# dual-mux.net
KiCad netlist of a schematic drawn in EAGLE
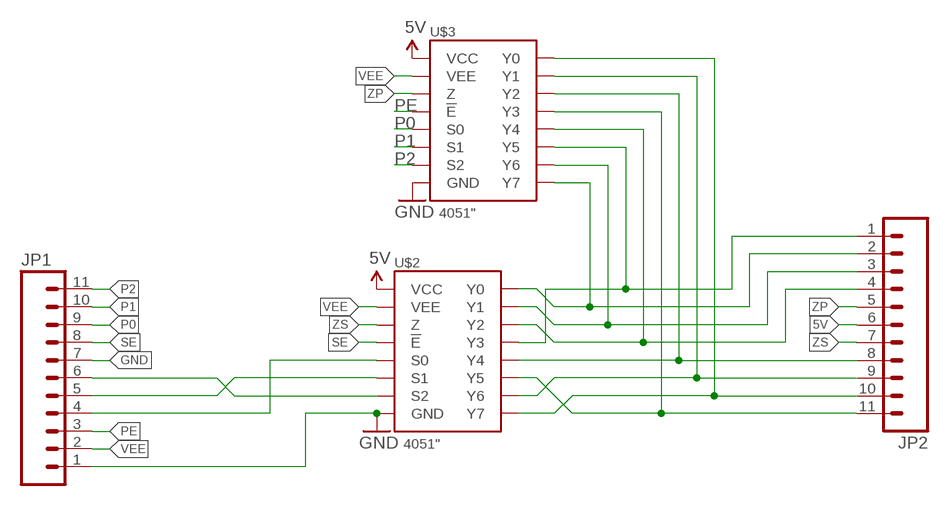
[diagram p0: schematic, sheet 1]

(export (version "E")
  (design (tool "Eeschema 10.0.6"))
  (components
    (comp (ref "JP1")
      (value "M11LONGPADS")
      (footprint "eagle-import:1X11_LONGPADS")
      (libsource (lib "eagle-import") (part "M11LONGPADS"))
    )
    (comp (ref "JP2")
      (value "M11LONGPADS")
      (footprint "eagle-import:1X11_LONGPADS")
      (libsource (lib "eagle-import") (part "M11LONGPADS"))
    )
    (comp (ref "U$2")
      (value "4051\"")
      (footprint "eagle-import:TSSOP-16")
      (libsource (lib "eagle-import") (part "4051{dblquote}"))
    )
    (comp (ref "U$3")
      (value "4051\"")
      (footprint "eagle-import:TSSOP-16")
      (libsource (lib "eagle-import") (part "4051{dblquote}"))
    )
  )
  (nets
    (net (code "1") (name "5V") (class "Default")
      (node (ref "JP2") (pin "6") (pinfunction "6_6") (pintype "passive"))
      (node (ref "U$2") (pin "P$16") (pinfunction "VCC_P$16") (pintype "bidirectional"))
      (node (ref "U$3") (pin "P$16") (pinfunction "VCC_P$16") (pintype "bidirectional"))
    )
    (net (code "2") (name "GND") (class "Default")
      (node (ref "JP1") (pin "1") (pinfunction "1_1") (pintype "passive"))
      (node (ref "JP1") (pin "7") (pinfunction "7_7") (pintype "passive"))
      (node (ref "U$2") (pin "P$8") (pinfunction "GND_P$8") (pintype "bidirectional"))
      (node (ref "U$3") (pin "P$8") (pinfunction "GND_P$8") (pintype "bidirectional"))
    )
    (net (code "3") (name "Net-(U$2-S0)") (class "Default")
      (node (ref "JP1") (pin "4") (pinfunction "4_4") (pintype "passive"))
      (node (ref "U$2") (pin "P$11") (pinfunction "S0_P$11") (pintype "bidirectional"))
    )
    (net (code "4") (name "Net-(U$2-S1)") (class "Default")
      (node (ref "JP1") (pin "5") (pinfunction "5_5") (pintype "passive"))
      (node (ref "U$2") (pin "P$10") (pinfunction "S1_P$10") (pintype "bidirectional"))
    )
    (net (code "5") (name "Net-(U$2-S2)") (class "Default")
      (node (ref "JP1") (pin "6") (pinfunction "6_6") (pintype "passive"))
      (node (ref "U$2") (pin "P$9") (pinfunction "S2_P$9") (pintype "bidirectional"))
    )
    (net (code "6") (name "Net-(U$2-Y0)") (class "Default")
      (node (ref "JP2") (pin "2") (pinfunction "2_2") (pintype "passive"))
      (node (ref "U$2") (pin "P$13") (pinfunction "Y0_P$13") (pintype "bidirectional"))
      (node (ref "U$3") (pin "P$4") (pinfunction "Y7_P$4") (pintype "bidirectional"))
    )
    (net (code "7") (name "Net-(U$2-Y1)") (class "Default")
      (node (ref "JP2") (pin "3") (pinfunction "3_3") (pintype "passive"))
      (node (ref "U$2") (pin "P$14") (pinfunction "Y1_P$14") (pintype "bidirectional"))
      (node (ref "U$3") (pin "P$2") (pinfunction "Y6_P$2") (pintype "bidirectional"))
    )
    (net (code "8") (name "Net-(U$2-Y2)") (class "Default")
      (node (ref "JP2") (pin "4") (pinfunction "4_4") (pintype "passive"))
      (node (ref "U$2") (pin "P$15") (pinfunction "Y2_P$15") (pintype "bidirectional"))
      (node (ref "U$3") (pin "P$1") (pinfunction "Y4_P$1") (pintype "bidirectional"))
    )
    (net (code "9") (name "Net-(U$2-Y3)") (class "Default")
      (node (ref "JP2") (pin "1") (pinfunction "1_1") (pintype "passive"))
      (node (ref "U$2") (pin "P$12") (pinfunction "Y3_P$12") (pintype "bidirectional"))
      (node (ref "U$3") (pin "P$5") (pinfunction "Y5_P$5") (pintype "bidirectional"))
    )
    (net (code "10") (name "Net-(U$2-Y4)") (class "Default")
      (node (ref "JP2") (pin "8") (pinfunction "8_8") (pintype "passive"))
      (node (ref "U$2") (pin "P$1") (pinfunction "Y4_P$1") (pintype "bidirectional"))
      (node (ref "U$3") (pin "P$15") (pinfunction "Y2_P$15") (pintype "bidirectional"))
    )
    (net (code "11") (name "Net-(U$2-Y5)") (class "Default")
      (node (ref "JP2") (pin "11") (pinfunction "11_11") (pintype "passive"))
      (node (ref "U$2") (pin "P$5") (pinfunction "Y5_P$5") (pintype "bidirectional"))
      (node (ref "U$3") (pin "P$12") (pinfunction "Y3_P$12") (pintype "bidirectional"))
    )
    (net (code "12") (name "Net-(U$2-Y6)") (class "Default")
      (node (ref "JP2") (pin "9") (pinfunction "9_9") (pintype "passive"))
      (node (ref "U$2") (pin "P$2") (pinfunction "Y6_P$2") (pintype "bidirectional"))
      (node (ref "U$3") (pin "P$14") (pinfunction "Y1_P$14") (pintype "bidirectional"))
    )
    (net (code "13") (name "Net-(U$2-Y7)") (class "Default")
      (node (ref "JP2") (pin "10") (pinfunction "10_10") (pintype "passive"))
      (node (ref "U$2") (pin "P$4") (pinfunction "Y7_P$4") (pintype "bidirectional"))
      (node (ref "U$3") (pin "P$13") (pinfunction "Y0_P$13") (pintype "bidirectional"))
    )
    (net (code "14") (name "P0") (class "Default")
      (node (ref "JP1") (pin "9") (pinfunction "9_9") (pintype "passive"))
      (node (ref "U$3") (pin "P$11") (pinfunction "S0_P$11") (pintype "bidirectional"))
    )
    (net (code "15") (name "P1") (class "Default")
      (node (ref "JP1") (pin "10") (pinfunction "10_10") (pintype "passive"))
      (node (ref "U$3") (pin "P$10") (pinfunction "S1_P$10") (pintype "bidirectional"))
    )
    (net (code "16") (name "P2") (class "Default")
      (node (ref "JP1") (pin "11") (pinfunction "11_11") (pintype "passive"))
      (node (ref "U$3") (pin "P$9") (pinfunction "S2_P$9") (pintype "bidirectional"))
    )
    (net (code "17") (name "PE") (class "Default")
      (node (ref "JP1") (pin "3") (pinfunction "3_3") (pintype "passive"))
      (node (ref "U$3") (pin "P$6") (pinfunction "~{E}_P$6") (pintype "bidirectional"))
    )
    (net (code "18") (name "SE") (class "Default")
      (node (ref "JP1") (pin "8") (pinfunction "8_8") (pintype "passive"))
      (node (ref "U$2") (pin "P$6") (pinfunction "~{E}_P$6") (pintype "bidirectional"))
    )
    (net (code "19") (name "VEE") (class "Default")
      (node (ref "JP1") (pin "2") (pinfunction "2_2") (pintype "passive"))
      (node (ref "U$2") (pin "P$7") (pinfunction "VEE_P$7") (pintype "bidirectional"))
      (node (ref "U$3") (pin "P$7") (pinfunction "VEE_P$7") (pintype "bidirectional"))
    )
    (net (code "20") (name "ZP") (class "Default")
      (node (ref "JP2") (pin "5") (pinfunction "5_5") (pintype "passive"))
      (node (ref "U$3") (pin "P$3") (pinfunction "Z_P$3") (pintype "bidirectional"))
    )
    (net (code "21") (name "ZS") (class "Default")
      (node (ref "JP2") (pin "7") (pinfunction "7_7") (pintype "passive"))
      (node (ref "U$2") (pin "P$3") (pinfunction "Z_P$3") (pintype "bidirectional"))
    )
  )
)
